# Outlet2.net
KiCad netlist of a schematic drawn in EAGLE
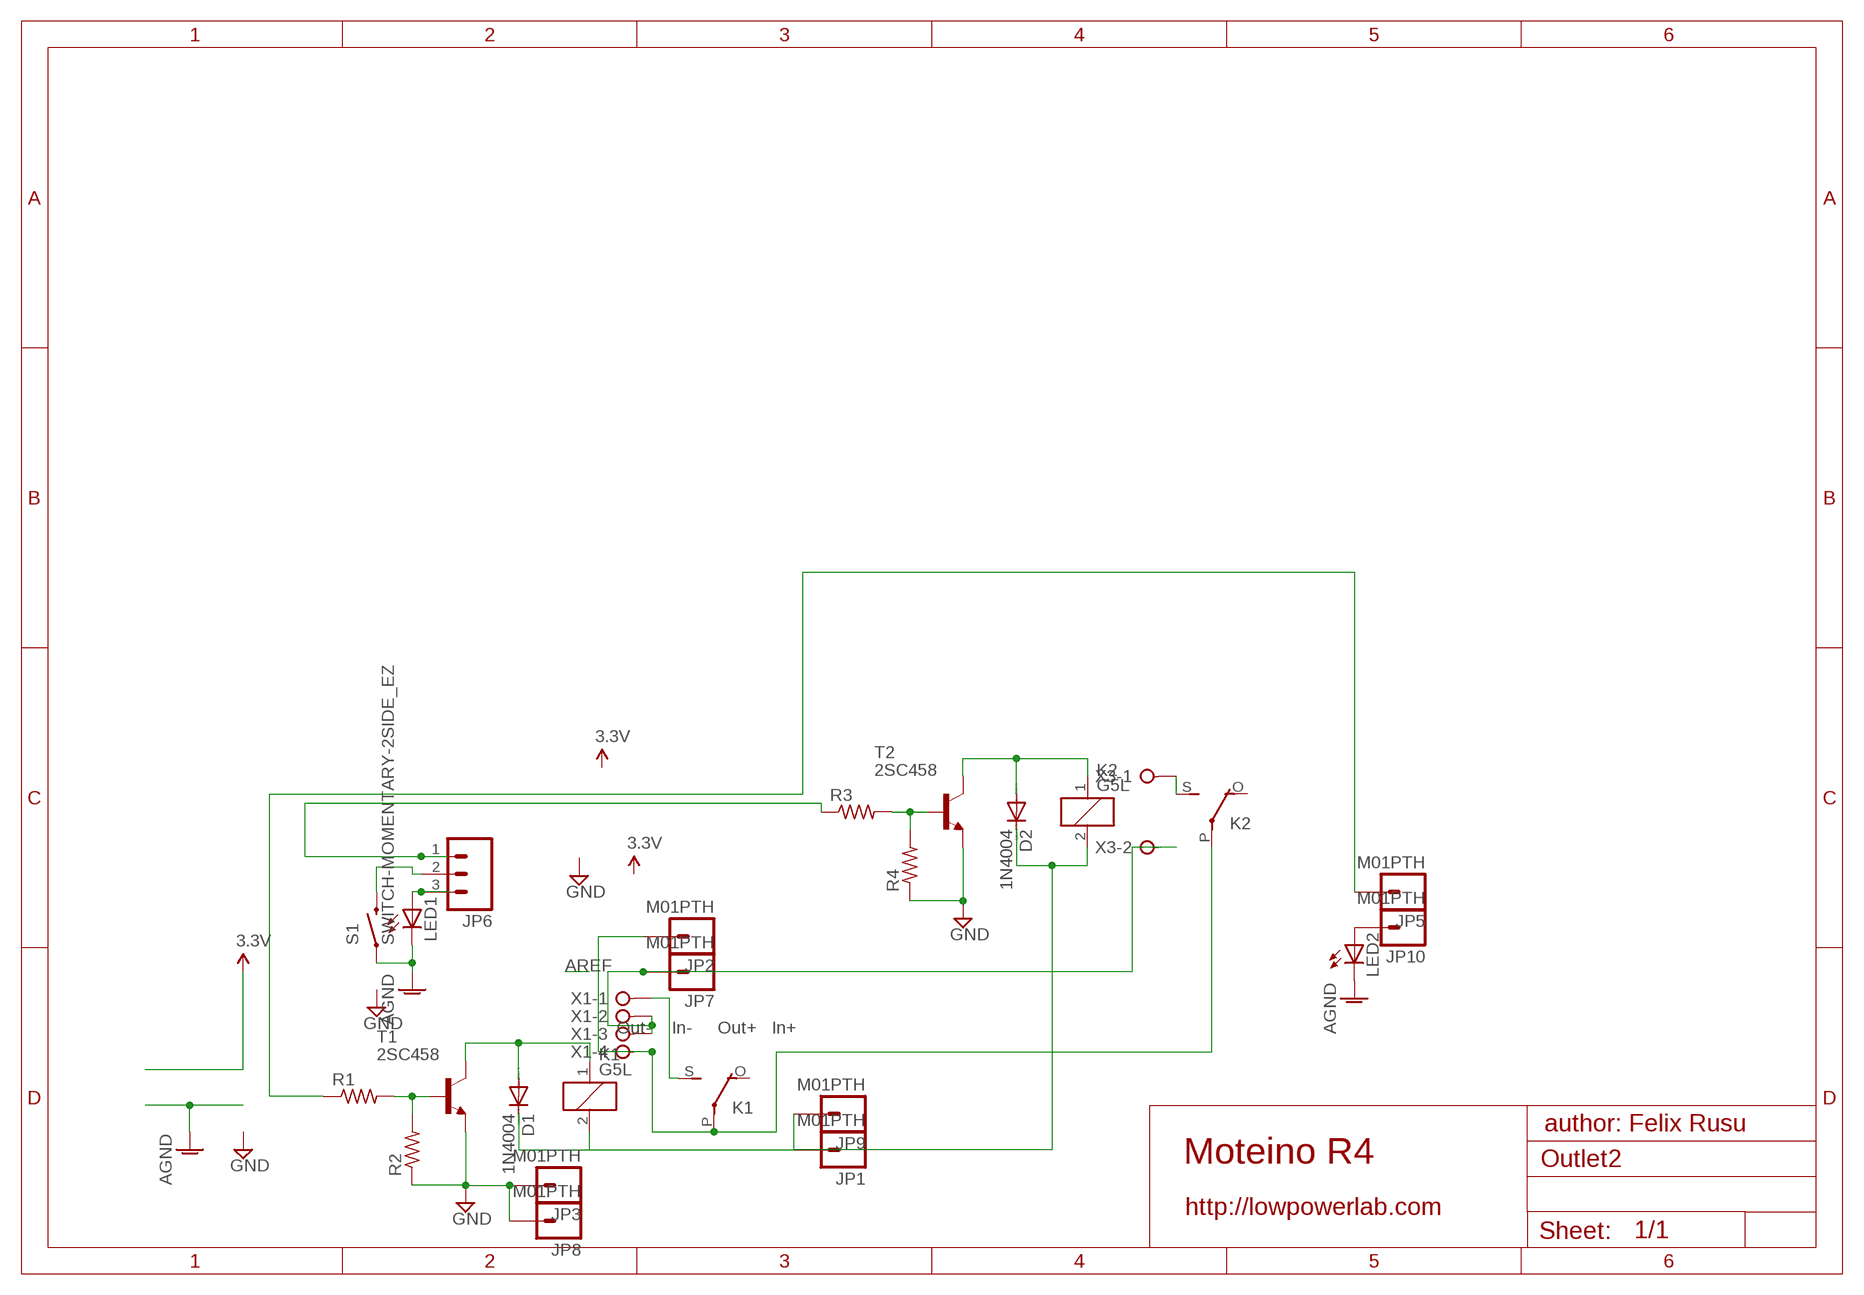
[diagram p0: schematic, sheet 1]

(export (version "E")
  (design (tool "Eeschema 10.0.6"))
  (components
    (comp (ref "D1")
      (value "1N4004")
      (footprint "eagle-import:DO41-10")
      (libsource (lib "eagle-import") (part "1N4004"))
    )
    (comp (ref "D2")
      (value "1N4004")
      (footprint "eagle-import:DO41-10")
      (libsource (lib "eagle-import") (part "1N4004"))
    )
    (comp (ref "JP1")
      (value "M01PTH")
      (footprint "eagle-import:1X01")
      (libsource (lib "eagle-import") (part "M01PTH"))
    )
    (comp (ref "JP2")
      (value "M01PTH")
      (footprint "eagle-import:1X01")
      (libsource (lib "eagle-import") (part "M01PTH"))
    )
    (comp (ref "JP3")
      (value "M01PTH")
      (footprint "eagle-import:1X01")
      (libsource (lib "eagle-import") (part "M01PTH"))
    )
    (comp (ref "JP5")
      (value "M01PTH")
      (footprint "eagle-import:1X01")
      (libsource (lib "eagle-import") (part "M01PTH"))
    )
    (comp (ref "JP6")
      (value "M03PTH")
      (footprint "eagle-import:1X03")
      (libsource (lib "eagle-import") (part "M03PTH"))
    )
    (comp (ref "JP7")
      (value "M01PTH")
      (footprint "eagle-import:1X01")
      (libsource (lib "eagle-import") (part "M01PTH"))
    )
    (comp (ref "JP8")
      (value "M01PTH")
      (footprint "eagle-import:1X01")
      (libsource (lib "eagle-import") (part "M01PTH"))
    )
    (comp (ref "JP9")
      (value "M01PTH")
      (footprint "eagle-import:1X01")
      (libsource (lib "eagle-import") (part "M01PTH"))
    )
    (comp (ref "JP10")
      (value "M01PTH")
      (footprint "eagle-import:1X01")
      (libsource (lib "eagle-import") (part "M01PTH"))
    )
    (comp (ref "K1")
      (value "G5L")
      (footprint "eagle-import:G5LE")
      (libsource (lib "eagle-import") (part "G5L"))
    )
    (comp (ref "K2")
      (value "G5L")
      (footprint "eagle-import:G5LE")
      (libsource (lib "eagle-import") (part "G5L"))
    )
    (comp (ref "LED1")
      (value "LED3MM")
      (footprint "eagle-import:LED3MM")
      (libsource (lib "eagle-import") (part "LED3MM"))
    )
    (comp (ref "LED2")
      (value "LED3MM")
      (footprint "eagle-import:LED3MM")
      (libsource (lib "eagle-import") (part "LED3MM"))
    )
    (comp (ref "R1")
      (value "R-US_0204/7")
      (footprint "eagle-import:0204_7")
      (libsource (lib "eagle-import") (part "R-US_0204/7"))
    )
    (comp (ref "R2")
      (value "R-US_0204/7")
      (footprint "eagle-import:0204_7")
      (libsource (lib "eagle-import") (part "R-US_0204/7"))
    )
    (comp (ref "R3")
      (value "R-US_0204/7")
      (footprint "eagle-import:0204_7")
      (libsource (lib "eagle-import") (part "R-US_0204/7"))
    )
    (comp (ref "R4")
      (value "R-US_0204/7")
      (footprint "eagle-import:0204_7")
      (libsource (lib "eagle-import") (part "R-US_0204/7"))
    )
    (comp (ref "S1")
      (value "SWITCH-MOMENTARY-2SIDE_EZ")
      (footprint "eagle-import:TACTILE-PTH-SIDEEZ")
      (libsource (lib "eagle-import") (part "SWITCH-MOMENTARY-2SIDE_EZ"))
    )
    (comp (ref "T1")
      (value "2SC458")
      (footprint "eagle-import:TO92-ECB")
      (libsource (lib "eagle-import") (part "2SC458"))
    )
    (comp (ref "T2")
      (value "2SC458")
      (footprint "eagle-import:TO92-ECB")
      (libsource (lib "eagle-import") (part "2SC458"))
    )
    (comp (ref "X1")
      (value "Out- In- Out+ In+")
      (footprint "eagle-import:W237-4P")
      (fields (field (name "MF") "In-") (field (name "MPN") "Out-"))
      (libsource (lib "eagle-import") (part "W237-04P"))
    )
    (comp (ref "X3")
      (value "W237-02P")
      (footprint "eagle-import:W237-132")
      (libsource (lib "eagle-import") (part "W237-02P"))
    )
  )
  (nets
    (net (code "3") (name "AGND") (class "Default")
      (node (ref "LED1") (pin "K") (pinfunction "C_K") (pintype "passive"))
      (node (ref "LED2") (pin "K") (pinfunction "C_K") (pintype "passive"))
      (node (ref "S1") (pin "1") (pinfunction "1_1") (pintype "passive"))
    )
    (net (code "4") (name "GND") (class "Default")
      (node (ref "JP3") (pin "1") (pinfunction "1_1") (pintype "passive"))
      (node (ref "JP8") (pin "1") (pinfunction "1_1") (pintype "passive"))
      (node (ref "R2") (pin "1") (pinfunction "1_1") (pintype "passive"))
      (node (ref "R4") (pin "1") (pinfunction "1_1") (pintype "passive"))
      (node (ref "T1") (pin "E") (pinfunction "E_E") (pintype "passive"))
      (node (ref "T2") (pin "E") (pinfunction "E_E") (pintype "passive"))
    )
    (net (code "5") (name "Net-(D1-PadA)") (class "Default")
      (node (ref "D1") (pin "A") (pinfunction "A_A") (pintype "passive"))
      (node (ref "K1") (pin "1") (pinfunction "1_1") (pintype "passive"))
      (node (ref "T1") (pin "C") (pinfunction "C_C") (pintype "passive"))
    )
    (net (code "6") (name "Net-(D1-PadC)") (class "Default")
      (node (ref "D1") (pin "C") (pinfunction "C_C") (pintype "passive"))
      (node (ref "D2") (pin "C") (pinfunction "C_C") (pintype "passive"))
      (node (ref "JP1") (pin "1") (pinfunction "1_1") (pintype "passive"))
      (node (ref "JP9") (pin "1") (pinfunction "1_1") (pintype "passive"))
      (node (ref "K1") (pin "2") (pinfunction "2_2") (pintype "passive"))
      (node (ref "K2") (pin "2") (pinfunction "2_2") (pintype "passive"))
    )
    (net (code "7") (name "Net-(D2-PadA)") (class "Default")
      (node (ref "D2") (pin "A") (pinfunction "A_A") (pintype "passive"))
      (node (ref "K2") (pin "1") (pinfunction "1_1") (pintype "passive"))
      (node (ref "T2") (pin "C") (pinfunction "C_C") (pintype "passive"))
    )
    (net (code "8") (name "Net-(JP5-Pad1)") (class "Default")
      (node (ref "JP5") (pin "1") (pinfunction "1_1") (pintype "passive"))
      (node (ref "R1") (pin "1") (pinfunction "1_1") (pintype "passive"))
    )
    (net (code "9") (name "Net-(JP6-Pad1)") (class "Default")
      (node (ref "JP6") (pin "1") (pinfunction "1_1") (pintype "passive"))
      (node (ref "R3") (pin "1") (pinfunction "1_1") (pintype "passive"))
    )
    (net (code "10") (name "Net-(JP6-Pad2)") (class "Default")
      (node (ref "JP6") (pin "2") (pinfunction "2_2") (pintype "passive"))
      (node (ref "S1") (pin "2") (pinfunction "2_2") (pintype "passive"))
    )
    (net (code "11") (name "Net-(JP6-Pad3)") (class "Default")
      (node (ref "JP6") (pin "3") (pinfunction "3_3") (pintype "passive"))
      (node (ref "LED1") (pin "A") (pinfunction "A_A") (pintype "passive"))
    )
    (net (code "12") (name "Net-(JP10-Pad1)") (class "Default")
      (node (ref "JP10") (pin "1") (pinfunction "1_1") (pintype "passive"))
      (node (ref "LED2") (pin "A") (pinfunction "A_A") (pintype "passive"))
    )
    (net (code "13") (name "Net-(R1-Pad2)") (class "Default")
      (node (ref "R1") (pin "2") (pinfunction "2_2") (pintype "passive"))
      (node (ref "R2") (pin "2") (pinfunction "2_2") (pintype "passive"))
      (node (ref "T1") (pin "B") (pinfunction "B_B") (pintype "passive"))
    )
    (net (code "14") (name "Net-(R3-Pad2)") (class "Default")
      (node (ref "R3") (pin "2") (pinfunction "2_2") (pintype "passive"))
      (node (ref "R4") (pin "2") (pinfunction "2_2") (pintype "passive"))
      (node (ref "T2") (pin "B") (pinfunction "B_B") (pintype "passive"))
    )
    (net (code "15") (name "Net-(X1A-KL)") (class "Default")
      (node (ref "K1") (pin "S") (pinfunction "S_S") (pintype "passive"))
      (node (ref "X1") (pin "1") (pinfunction "KL_1") (pintype "passive"))
    )
    (net (code "16") (name "Net-(X1B-KL)") (class "Default")
      (node (ref "JP7") (pin "1") (pinfunction "1_1") (pintype "passive"))
      (node (ref "X1") (pin "2") (pinfunction "KL_2") (pintype "passive"))
      (node (ref "X1") (pin "3") (pinfunction "KL_3") (pintype "passive"))
      (node (ref "X3") (pin "2") (pinfunction "KL_2") (pintype "passive"))
    )
    (net (code "17") (name "Net-(X1D-KL)") (class "Default")
      (node (ref "JP2") (pin "1") (pinfunction "1_1") (pintype "passive"))
      (node (ref "K1") (pin "P") (pinfunction "P_P") (pintype "passive"))
      (node (ref "K2") (pin "P") (pinfunction "P_P") (pintype "passive"))
      (node (ref "X1") (pin "4") (pinfunction "KL_4") (pintype "passive"))
    )
    (net (code "18") (name "Net-(X3A-KL)") (class "Default")
      (node (ref "K2") (pin "S") (pinfunction "S_S") (pintype "passive"))
      (node (ref "X3") (pin "1") (pinfunction "KL_1") (pintype "passive"))
    )
    (net (code "19") (name "unconnected-(K1-PadO)") (class "Default")
      (node (ref "K1") (pin "O") (pinfunction "O_O") (pintype "passive"))
    )
    (net (code "20") (name "unconnected-(K2-PadO)") (class "Default")
      (node (ref "K2") (pin "O") (pinfunction "O_O") (pintype "passive"))
    )
  )
)
